# MCU.net
KiCad netlist of a schematic drawn in Altium Designer
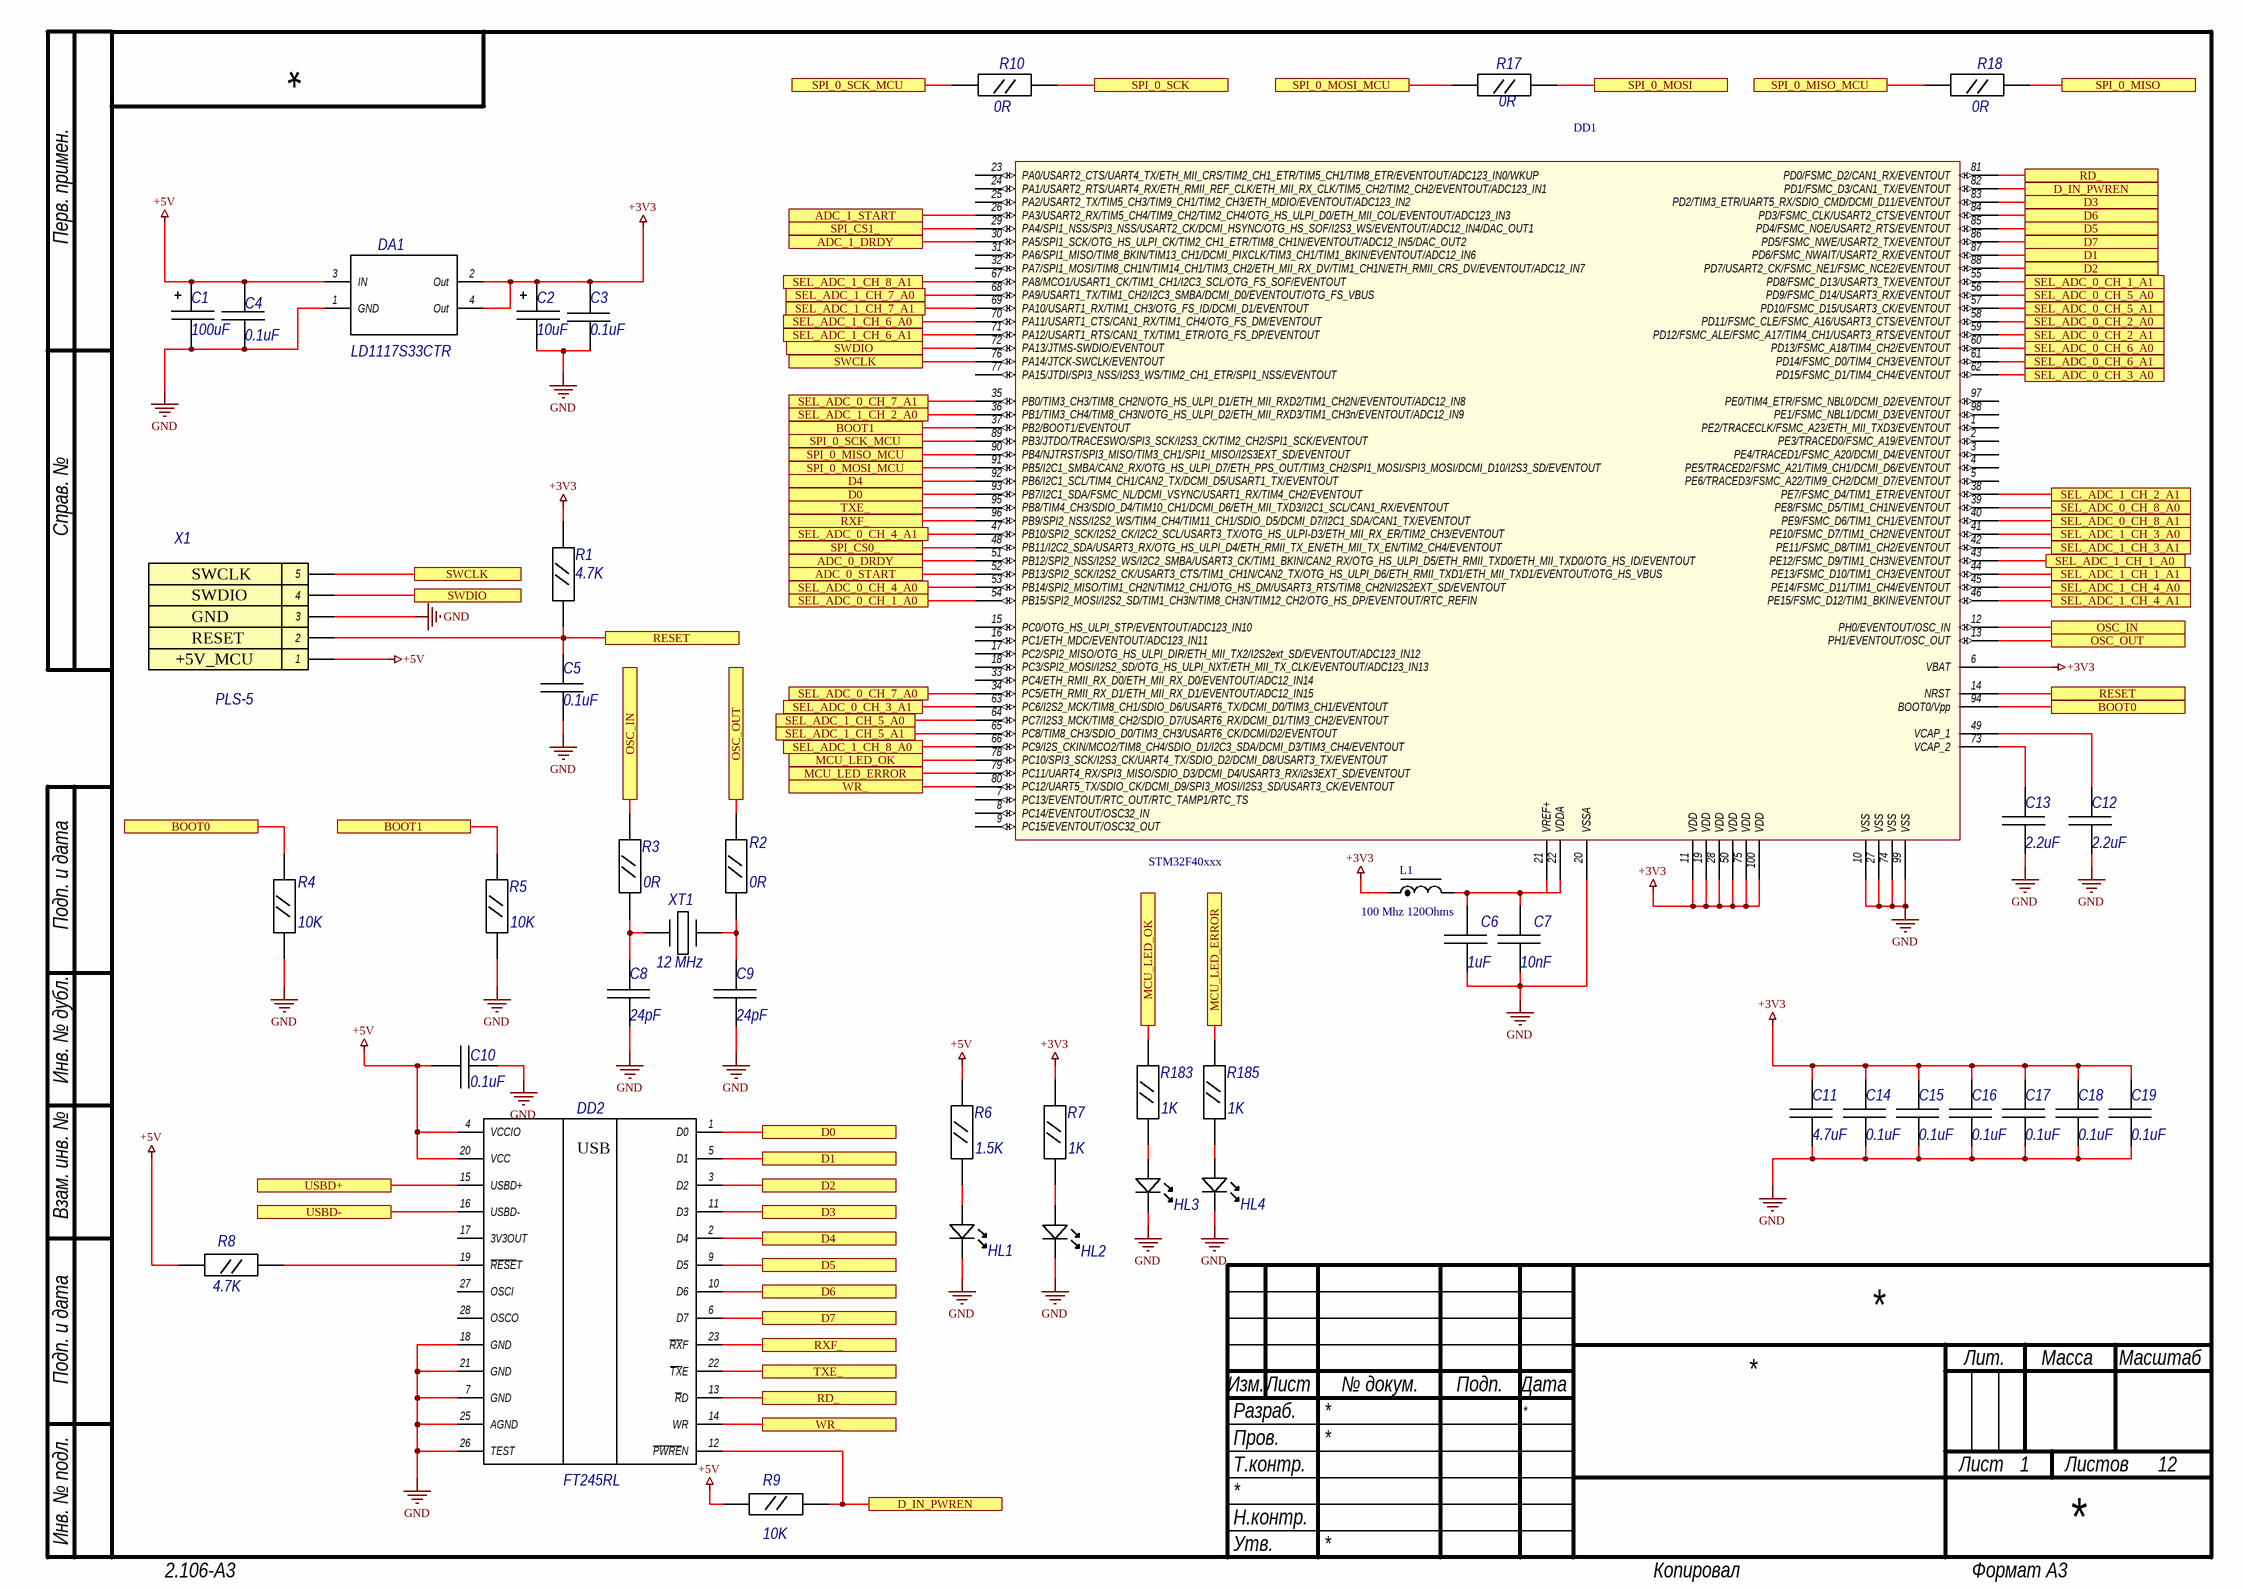
[diagram p0: MCU.SchDoc]

(export (version "E")
  (design (tool "Eeschema 10.0.6"))
  (components
    (comp (ref "C1")
      (value "100uF")
      (footprint "CT_SMD_A")
      (description "Capacitor tantalum")
      (libsource (lib "GOST") (part "CT_SMD_A"))
    )
    (comp (ref "C2")
      (value "10uF")
      (footprint "CT_SMD_A")
      (description "Capacitor tantalum")
      (libsource (lib "GOST") (part "CT_SMD_A"))
    )
    (comp (ref "C3")
      (value "0.1uF")
      (footprint "C0603")
      (description "Ceramic Capacitor SMD")
      (libsource (lib "GOST") (part "CC_SMD_0603"))
    )
    (comp (ref "C4")
      (value "0.1uF")
      (footprint "C0603")
      (description "Ceramic Capacitor SMD")
      (libsource (lib "GOST") (part "CC_SMD_0603"))
    )
    (comp (ref "C5")
      (value "0.1uF")
      (footprint "C0603")
      (description "Ceramic Capacitor SMD")
      (libsource (lib "GOST") (part "CC_SMD_0603"))
    )
    (comp (ref "C6")
      (value "1uF")
      (footprint "C0603")
      (description "Ceramic Capacitor SMD")
      (libsource (lib "GOST") (part "CC_SMD_0603"))
    )
    (comp (ref "C7")
      (value "10nF")
      (footprint "C0603")
      (description "Ceramic Capacitor SMD")
      (libsource (lib "GOST") (part "CC_SMD_0603"))
    )
    (comp (ref "C8")
      (value "24pF")
      (footprint "C0603")
      (description "Ceramic Capacitor SMD")
      (libsource (lib "GOST") (part "CC_SMD_0603"))
    )
    (comp (ref "C9")
      (value "24pF")
      (footprint "C0603")
      (description "Ceramic Capacitor SMD")
      (libsource (lib "GOST") (part "CC_SMD_0603"))
    )
    (comp (ref "C10")
      (value "0.1uF")
      (footprint "C0603")
      (description "Ceramic Capacitor SMD")
      (libsource (lib "GOST") (part "CC_SMD_0603"))
    )
    (comp (ref "C11")
      (value "4.7uF")
      (footprint "C0603")
      (description "Ceramic Capacitor SMD")
      (libsource (lib "GOST") (part "CC_SMD_0603"))
    )
    (comp (ref "C12")
      (value "2.2uF")
      (footprint "C0603")
      (description "Ceramic Capacitor SMD")
      (libsource (lib "GOST") (part "CC_SMD_0603"))
    )
    (comp (ref "C13")
      (value "2.2uF")
      (footprint "C0603")
      (description "Ceramic Capacitor SMD")
      (libsource (lib "GOST") (part "CC_SMD_0603"))
    )
    (comp (ref "C14")
      (value "0.1uF")
      (footprint "C0603")
      (description "Ceramic Capacitor SMD")
      (libsource (lib "GOST") (part "CC_SMD_0603"))
    )
    (comp (ref "C15")
      (value "0.1uF")
      (footprint "C0603")
      (description "Ceramic Capacitor SMD")
      (libsource (lib "GOST") (part "CC_SMD_0603"))
    )
    (comp (ref "C16")
      (value "0.1uF")
      (footprint "C0603")
      (description "Ceramic Capacitor SMD")
      (libsource (lib "GOST") (part "CC_SMD_0603"))
    )
    (comp (ref "C17")
      (value "0.1uF")
      (footprint "C0603")
      (description "Ceramic Capacitor SMD")
      (libsource (lib "GOST") (part "CC_SMD_0603"))
    )
    (comp (ref "C18")
      (value "0.1uF")
      (footprint "C0603")
      (description "Ceramic Capacitor SMD")
      (libsource (lib "GOST") (part "CC_SMD_0603"))
    )
    (comp (ref "C19")
      (value "0.1uF")
      (footprint "C0603")
      (description "Ceramic Capacitor SMD")
      (libsource (lib "GOST") (part "CC_SMD_0603"))
    )
    (comp (ref "DA1")
      (value "LD1117S33CTR")
      (footprint "SOT-223(DCY)")
      (description "LDO")
      (libsource (lib "GOST") (part "LD1117S33CTR"))
    )
    (comp (ref "DD1")
      (value "STM32F40xxx")
      (footprint "QFP50P1600X1600X160-100N")
      (description "ARM CortexM4 32b")
      (libsource (lib "GOST") (part "STM32F40xxx"))
    )
    (comp (ref "DD2")
      (value "FT245RL")
      (footprint "SSOP-28N")
      (description "USB to parallel FIFO interface")
      (fields (field (name "MANUFACTURER") "FTDI"))
      (libsource (lib "GOST") (part "FT245RL"))
    )
    (comp (ref "HL1")
      (value "GREEN")
      (footprint "LED_0603")
      (description "LED GREEN SMD 0603")
      (fields (field (name "PARTNUMBER") "FYLS-0603PGC"))
      (libsource (lib "GOST") (part "LED_G_SMD_0603"))
    )
    (comp (ref "HL2")
      (value "GREEN")
      (footprint "LED_0603")
      (description "LED GREEN SMD 0603")
      (fields (field (name "PARTNUMBER") "FYLS-0603PGC"))
      (libsource (lib "GOST") (part "LED_G_SMD_0603"))
    )
    (comp (ref "HL3")
      (value "GREEN")
      (footprint "LED_0603")
      (description "LED GREEN SMD 0603")
      (fields (field (name "PARTNUMBER") "FYLS-0603PGC"))
      (libsource (lib "GOST") (part "LED_G_SMD_0603"))
    )
    (comp (ref "HL4")
      (value "GREEN")
      (footprint "LED_0603")
      (description "LED GREEN SMD 0603")
      (fields (field (name "PARTNUMBER") "FYLS-0603PGC"))
      (libsource (lib "GOST") (part "LED_G_SMD_0603"))
    )
    (comp (ref "L1")
      (value "100 Mhz 120Ohms")
      (footprint "0805")
      (description "FerriteBead")
      (fields (field (name "PARTNUMBER") "BLM21PG121SN1D"))
      (libsource (lib "GOST") (part "FerriteBead_0805"))
    )
    (comp (ref "R1")
      (value "4.7K")
      (footprint "R0603")
      (description "Resistor SMD")
      (libsource (lib "GOST") (part "R0603"))
    )
    (comp (ref "R2")
      (value "0R")
      (footprint "R0603")
      (description "Resistor SMD")
      (libsource (lib "GOST") (part "R0603"))
    )
    (comp (ref "R3")
      (value "0R")
      (footprint "R0603")
      (description "Resistor SMD")
      (libsource (lib "GOST") (part "R0603"))
    )
    (comp (ref "R4")
      (value "10K")
      (footprint "R0603")
      (description "Resistor SMD")
      (libsource (lib "GOST") (part "R0603"))
    )
    (comp (ref "R5")
      (value "10K")
      (footprint "R0603")
      (description "Resistor SMD")
      (libsource (lib "GOST") (part "R0603"))
    )
    (comp (ref "R6")
      (value "1.5K")
      (footprint "R0603")
      (description "Resistor SMD")
      (libsource (lib "GOST") (part "R0603"))
    )
    (comp (ref "R7")
      (value "1K")
      (footprint "R0603")
      (description "Resistor SMD")
      (libsource (lib "GOST") (part "R0603"))
    )
    (comp (ref "R8")
      (value "4.7K")
      (footprint "R0603")
      (description "Resistor SMD")
      (libsource (lib "GOST") (part "R0603"))
    )
    (comp (ref "R9")
      (value "10K")
      (footprint "R0603")
      (description "Resistor SMD")
      (libsource (lib "GOST") (part "R0603"))
    )
    (comp (ref "R10")
      (value "0R")
      (footprint "R0603")
      (description "Resistor SMD")
      (libsource (lib "") (part "R0603_1"))
    )
    (comp (ref "R17")
      (value "0R")
      (footprint "R0603")
      (description "Resistor SMD")
      (libsource (lib "") (part "R0603_1"))
    )
    (comp (ref "R18")
      (value "0R")
      (footprint "R0603")
      (description "Resistor SMD")
      (libsource (lib "") (part "R0603_1"))
    )
    (comp (ref "R183")
      (value "1K")
      (footprint "R0603")
      (description "Resistor SMD")
      (libsource (lib "GOST") (part "R0603"))
    )
    (comp (ref "R185")
      (value "1K")
      (footprint "R0603")
      (description "Resistor SMD")
      (libsource (lib "GOST") (part "R0603"))
    )
    (comp (ref "X1")
      (value "PLS-5")
      (footprint "PLS-5")
      (description "5 pin connector, 2.54 step")
      (fields (field (name "PARTNUMBER") "825433-5"))
      (libsource (lib "GOST") (part "PLS-5"))
    )
    (comp (ref "XT1")
      (value "12 MHz")
      (footprint "HC49/US")
      (description "Quarz ESR 50 Ohms, Frequency Stability ±30ppm, Load Capacitance 18 pF")
      (fields (field (name "PARTNUMBER") "J49SML-F-G-G-K-12M0"))
      (libsource (lib "GOST") (part "Quarz HC-49/US 12 MHz"))
    )
  )
  (nets
    (net (code "1") (name "+3V3") (class "Default")
      (node (ref "C11") (pin "2") (pinfunction "2_2") (pintype "passive"))
      (node (ref "C14") (pin "2") (pinfunction "2_2") (pintype "passive"))
      (node (ref "C15") (pin "2") (pinfunction "2_2") (pintype "passive"))
      (node (ref "C16") (pin "2") (pinfunction "2_2") (pintype "passive"))
      (node (ref "C17") (pin "2") (pinfunction "2_2") (pintype "passive"))
      (node (ref "C18") (pin "2") (pinfunction "2_2") (pintype "passive"))
      (node (ref "C19") (pin "2") (pinfunction "2_2") (pintype "passive"))
      (node (ref "C2") (pin "1") (pinfunction "1_1") (pintype "passive"))
      (node (ref "C3") (pin "2") (pinfunction "2_2") (pintype "passive"))
      (node (ref "DA1") (pin "2") (pinfunction "Out_2") (pintype "passive"))
      (node (ref "DA1") (pin "4") (pinfunction "Out_4") (pintype "passive"))
      (node (ref "DD1") (pin "100") (pinfunction "VDD_100") (pintype "power_in"))
      (node (ref "DD1") (pin "11") (pinfunction "VDD_11") (pintype "power_in"))
      (node (ref "DD1") (pin "19") (pinfunction "VDD_19") (pintype "power_in"))
      (node (ref "DD1") (pin "28") (pinfunction "VDD_28") (pintype "power_in"))
      (node (ref "DD1") (pin "50") (pinfunction "VDD_50") (pintype "power_in"))
      (node (ref "DD1") (pin "6") (pinfunction "VBAT_6") (pintype "power_in"))
      (node (ref "DD1") (pin "75") (pinfunction "VDD_75") (pintype "power_in"))
      (node (ref "L1") (pin "1") (pinfunction "1_1") (pintype "passive"))
      (node (ref "R1") (pin "2") (pinfunction "2_2") (pintype "passive"))
      (node (ref "R7") (pin "2") (pinfunction "2_2") (pintype "passive"))
    )
    (net (code "2") (name "+5V") (class "Default")
      (node (ref "C1") (pin "1") (pinfunction "1_1") (pintype "passive"))
      (node (ref "C10") (pin "2") (pinfunction "2_2") (pintype "passive"))
      (node (ref "C4") (pin "2") (pinfunction "2_2") (pintype "passive"))
      (node (ref "DA1") (pin "3") (pinfunction "IN_3") (pintype "power_in"))
      (node (ref "DD2") (pin "20") (pinfunction "VCC_20") (pintype "passive"))
      (node (ref "DD2") (pin "4") (pinfunction "VCCIO_4") (pintype "passive"))
      (node (ref "R6") (pin "2") (pinfunction "2_2") (pintype "passive"))
      (node (ref "R8") (pin "2") (pinfunction "2_2") (pintype "passive"))
      (node (ref "R9") (pin "1") (pinfunction "1_1") (pintype "passive"))
      (node (ref "X1") (pin "1") (pinfunction "1_1") (pintype "passive"))
    )
    (net (code "3") (name "/ADC_0_DRDY") (class "Default")
      (node (ref "DD1") (pin "51") (pinfunction "PB12/SPI2_NSS/I2S2_WS/I2C2_SMBA/USART3_CK/TIM1_BKIN/CAN2_RX/OTG_HS_ULPI_D5/ETH_RMII_TXD0/ETH_MII_TXD0/OTG_HS_ID/EVENTOUT_51") (pintype "bidirectional"))
    )
    (net (code "4") (name "/ADC_0_START") (class "Default")
      (node (ref "DD1") (pin "52") (pinfunction "PB13/SPI2_SCK/I2S2_CK/USART3_CTS/TIM1_CH1N/CAN2_TX/OTG_HS_ULPI_D6/ETH_RMII_TXD1/ETH_MII_TXD1/EVENTOUT/OTG_HS_VBUS_52") (pintype "bidirectional"))
    )
    (net (code "5") (name "/ADC_1_DRDY") (class "Default")
      (node (ref "DD1") (pin "30") (pinfunction "PA5/SPI1_SCK/OTG_HS_ULPI_CK/TIM2_CH1_ETR/TIM8_CH1N/EVENTOUT/ADC12_IN5/DAC_OUT2_30") (pintype "bidirectional"))
    )
    (net (code "6") (name "/ADC_1_START") (class "Default")
      (node (ref "DD1") (pin "26") (pinfunction "PA3/USART2_RX/TIM5_CH4/TIM9_CH2/TIM2_CH4/OTG_HS_ULPI_D0/ETH_MII_COL/EVENTOUT/ADC123_IN3_26") (pintype "bidirectional"))
    )
    (net (code "7") (name "/BOOT0") (class "Default")
      (node (ref "DD1") (pin "94") (pinfunction "BOOT0/Vpp_94") (pintype "power_in"))
      (node (ref "R4") (pin "2") (pinfunction "2_2") (pintype "passive"))
    )
    (net (code "8") (name "/BOOT1") (class "Default")
      (node (ref "DD1") (pin "37") (pinfunction "PB2/BOOT1/EVENTOUT_37") (pintype "bidirectional"))
      (node (ref "R5") (pin "2") (pinfunction "2_2") (pintype "passive"))
    )
    (net (code "9") (name "/D0") (class "Default")
      (node (ref "DD1") (pin "93") (pinfunction "PB7/I2C1_SDA/FSMC_NL/DCMI_VSYNC/USART1_RX/TIM4_CH2/EVENTOUT_93") (pintype "bidirectional"))
      (node (ref "DD2") (pin "1") (pinfunction "D0_1") (pintype "passive"))
    )
    (net (code "10") (name "/D1") (class "Default")
      (node (ref "DD1") (pin "87") (pinfunction "PD6/FSMC_NWAIT/USART2_RX/EVENTOUT_87") (pintype "bidirectional"))
      (node (ref "DD2") (pin "5") (pinfunction "D1_5") (pintype "passive"))
    )
    (net (code "11") (name "/D2") (class "Default")
      (node (ref "DD1") (pin "88") (pinfunction "PD7/USART2_CK/FSMC_NE1/FSMC_NCE2/EVENTOUT_88") (pintype "bidirectional"))
      (node (ref "DD2") (pin "3") (pinfunction "D2_3") (pintype "passive"))
    )
    (net (code "12") (name "/D3") (class "Default")
      (node (ref "DD1") (pin "83") (pinfunction "PD2/TIM3_ETR/UART5_RX/SDIO_CMD/DCMI_D11/EVENTOUT_83") (pintype "bidirectional"))
      (node (ref "DD2") (pin "11") (pinfunction "D3_11") (pintype "passive"))
    )
    (net (code "13") (name "/D4") (class "Default")
      (node (ref "DD1") (pin "92") (pinfunction "PB6/I2C1_SCL/TIM4_CH1/CAN2_TX/DCMI_D5/USART1_TX/EVENTOUT_92") (pintype "bidirectional"))
      (node (ref "DD2") (pin "2") (pinfunction "D4_2") (pintype "passive"))
    )
    (net (code "14") (name "/D5") (class "Default")
      (node (ref "DD1") (pin "85") (pinfunction "PD4/FSMC_NOE/USART2_RTS/EVENTOUT_85") (pintype "bidirectional"))
      (node (ref "DD2") (pin "9") (pinfunction "D5_9") (pintype "passive"))
    )
    (net (code "15") (name "/D6") (class "Default")
      (node (ref "DD1") (pin "84") (pinfunction "PD3/FSMC_CLK/USART2_CTS/EVENTOUT_84") (pintype "bidirectional"))
      (node (ref "DD2") (pin "10") (pinfunction "D6_10") (pintype "passive"))
    )
    (net (code "16") (name "/D7") (class "Default")
      (node (ref "DD1") (pin "86") (pinfunction "PD5/FSMC_NWE/USART2_TX/EVENTOUT_86") (pintype "bidirectional"))
      (node (ref "DD2") (pin "6") (pinfunction "D7_6") (pintype "passive"))
    )
    (net (code "17") (name "/D_IN_PWREN") (class "Default")
      (node (ref "DD1") (pin "82") (pinfunction "PD1/FSMC_D3/CAN1_TX/EVENTOUT_82") (pintype "bidirectional"))
      (node (ref "DD2") (pin "12") (pinfunction "~{PWRE}N_12") (pintype "passive"))
      (node (ref "R9") (pin "2") (pinfunction "2_2") (pintype "passive"))
    )
    (net (code "18") (name "/MCU_LED_ERROR") (class "Default")
      (node (ref "DD1") (pin "79") (pinfunction "PC11/UART4_RX/SPI3_MISO/SDIO_D3/DCMI_D4/USART3_RX/i2s3EXT_SD/EVENTOUT_79") (pintype "bidirectional"))
      (node (ref "R185") (pin "2") (pinfunction "2_2") (pintype "passive"))
    )
    (net (code "19") (name "/MCU_LED_OK") (class "Default")
      (node (ref "DD1") (pin "78") (pinfunction "PC10/SPI3_SCK/I2S3_CK/UART4_TX/SDIO_D2/DCMI_D8/USART3_TX/EVENTOUT_78") (pintype "bidirectional"))
      (node (ref "R183") (pin "2") (pinfunction "2_2") (pintype "passive"))
    )
    (net (code "20") (name "/OSC_IN") (class "Default")
      (node (ref "DD1") (pin "12") (pinfunction "PH0/EVENTOUT/OSC_IN_12") (pintype "bidirectional"))
      (node (ref "R3") (pin "2") (pinfunction "2_2") (pintype "passive"))
    )
    (net (code "21") (name "/OSC_OUT") (class "Default")
      (node (ref "DD1") (pin "13") (pinfunction "PH1/EVENTOUT/OSC_OUT_13") (pintype "bidirectional"))
      (node (ref "R2") (pin "2") (pinfunction "2_2") (pintype "passive"))
    )
    (net (code "22") (name "/RD_") (class "Default")
      (node (ref "DD1") (pin "81") (pinfunction "PD0/FSMC_D2/CAN1_RX/EVENTOUT_81") (pintype "bidirectional"))
      (node (ref "DD2") (pin "13") (pinfunction "~{R}D_13") (pintype "passive"))
    )
    (net (code "23") (name "/RESET") (class "Default")
      (node (ref "C5") (pin "2") (pinfunction "2_2") (pintype "passive"))
      (node (ref "DD1") (pin "14") (pinfunction "NRST_14") (pintype "power_in"))
      (node (ref "R1") (pin "1") (pinfunction "1_1") (pintype "passive"))
      (node (ref "X1") (pin "2") (pinfunction "2_2") (pintype "passive"))
    )
    (net (code "24") (name "/RXF_") (class "Default")
      (node (ref "DD1") (pin "96") (pinfunction "PB9/SPI2_NSS/I2S2_WS/TIM4_CH4/TIM11_CH1/SDIO_D5/DCMI_D7/I2C1_SDA/CAN1_TX/EVENTOUT_96") (pintype "bidirectional"))
      (node (ref "DD2") (pin "23") (pinfunction "~{RX}F_23") (pintype "passive"))
    )
    (net (code "25") (name "/SEL_ADC_0_CH_1_A0") (class "Default")
      (node (ref "DD1") (pin "54") (pinfunction "PB15/SPI2_MOSI/I2S2_SD/TIM1_CH3N/TIM8_CH3N/TIM12_CH2/OTG_HS_DP/EVENTOUT/RTC_REFIN_54") (pintype "bidirectional"))
    )
    (net (code "26") (name "/SEL_ADC_0_CH_1_A1") (class "Default")
      (node (ref "DD1") (pin "55") (pinfunction "PD8/FSMC_D13/USART3_TX/EVENTOUT_55") (pintype "bidirectional"))
    )
    (net (code "27") (name "/SEL_ADC_0_CH_2_A0") (class "Default")
      (node (ref "DD1") (pin "58") (pinfunction "PD11/FSMC_CLE/FSMC_A16/USART3_CTS/EVENTOUT_58") (pintype "bidirectional"))
    )
    (net (code "28") (name "/SEL_ADC_0_CH_2_A1") (class "Default")
      (node (ref "DD1") (pin "59") (pinfunction "PD12/FSMC_ALE/FSMC_A17/TIM4_CH1/USART3_RTS/EVENTOUT_59") (pintype "bidirectional"))
    )
    (net (code "29") (name "/SEL_ADC_0_CH_3_A0") (class "Default")
      (node (ref "DD1") (pin "62") (pinfunction "PD15/FSMC_D1/TIM4_CH4/EVENTOUT_62") (pintype "bidirectional"))
    )
    (net (code "30") (name "/SEL_ADC_0_CH_3_A1") (class "Default")
      (node (ref "DD1") (pin "63") (pinfunction "PC6/I2S2_MCK/TIM8_CH1/SDIO_D6/USART6_TX/DCMI_D0/TIM3_CH1/EVENTOUT_63") (pintype "bidirectional"))
    )
    (net (code "31") (name "/SEL_ADC_0_CH_4_A0") (class "Default")
      (node (ref "DD1") (pin "53") (pinfunction "PB14/SPI2_MISO/TIM1_CH2N/TIM12_CH1/OTG_HS_DM/USART3_RTS/TIM8_CH2N/I2S2EXT_SD/EVENTOUT_53") (pintype "bidirectional"))
    )
    (net (code "32") (name "/SEL_ADC_0_CH_4_A1") (class "Default")
      (node (ref "DD1") (pin "47") (pinfunction "PB10/SPI2_SCK/I2S2_CK/I2C2_SCL/USART3_TX/OTG_HS_ULPI-D3/ETH_MII_RX_ER/TIM2_CH3/EVENTOUT_47") (pintype "bidirectional"))
    )
    (net (code "33") (name "/SEL_ADC_0_CH_5_A0") (class "Default")
      (node (ref "DD1") (pin "56") (pinfunction "PD9/FSMC_D14/USART3_RX/EVENTOUT_56") (pintype "bidirectional"))
    )
    (net (code "34") (name "/SEL_ADC_0_CH_5_A1") (class "Default")
      (node (ref "DD1") (pin "57") (pinfunction "PD10/FSMC_D15/USART3_CK/EVENTOUT_57") (pintype "bidirectional"))
    )
    (net (code "35") (name "/SEL_ADC_0_CH_6_A0") (class "Default")
      (node (ref "DD1") (pin "60") (pinfunction "PD13/FSMC_A18/TIM4_CH2/EVENTOUT_60") (pintype "bidirectional"))
    )
    (net (code "36") (name "/SEL_ADC_0_CH_6_A1") (class "Default")
      (node (ref "DD1") (pin "61") (pinfunction "PD14/FSMC_D0/TIM4_CH3/EVENTOUT_61") (pintype "bidirectional"))
    )
    (net (code "37") (name "/SEL_ADC_0_CH_7_A0") (class "Default")
      (node (ref "DD1") (pin "34") (pinfunction "PC5/ETH_RMII_RX_D1/ETH_MII_RX_D1/EVENTOUT/ADC12_IN15_34") (pintype "bidirectional"))
    )
    (net (code "38") (name "/SEL_ADC_0_CH_7_A1") (class "Default")
      (node (ref "DD1") (pin "35") (pinfunction "PB0/TIM3_CH3/TIM8_CH2N/OTG_HS_ULPI_D1/ETH_MII_RXD2/TIM1_CH2N/EVENTOUT/ADC12_IN8_35") (pintype "bidirectional"))
    )
    (net (code "39") (name "/SEL_ADC_0_CH_8_A0") (class "Default")
      (node (ref "DD1") (pin "39") (pinfunction "PE8/FSMC_D5/TIM1_CH1N/EVENTOUT_39") (pintype "bidirectional"))
    )
    (net (code "40") (name "/SEL_ADC_0_CH_8_A1") (class "Default")
      (node (ref "DD1") (pin "40") (pinfunction "PE9/FSMC_D6/TIM1_CH1/EVENTOUT_40") (pintype "bidirectional"))
    )
    (net (code "41") (name "/SEL_ADC_1_CH_1_A0") (class "Default")
      (node (ref "DD1") (pin "43") (pinfunction "PE12/FSMC_D9/TIM1_CH3N/EVENTOUT_43") (pintype "bidirectional"))
    )
    (net (code "42") (name "/SEL_ADC_1_CH_1_A1") (class "Default")
      (node (ref "DD1") (pin "44") (pinfunction "PE13/FSMC_D10/TIM1_CH3/EVENTOUT_44") (pintype "bidirectional"))
    )
    (net (code "43") (name "/SEL_ADC_1_CH_2_A0") (class "Default")
      (node (ref "DD1") (pin "36") (pinfunction "PB1/TIM3_CH4/TIM8_CH3N/OTG_HS_ULPI_D2/ETH_MII_RXD3/TIM1_CH3n/EVENTOUT/ADC12_IN9_36") (pintype "bidirectional"))
    )
    (net (code "44") (name "/SEL_ADC_1_CH_2_A1") (class "Default")
      (node (ref "DD1") (pin "38") (pinfunction "PE7/FSMC_D4/TIM1_ETR/EVENTOUT_38") (pintype "bidirectional"))
    )
    (net (code "45") (name "/SEL_ADC_1_CH_3_A0") (class "Default")
      (node (ref "DD1") (pin "41") (pinfunction "PE10/FSMC_D7/TIM1_CH2N/EVENTOUT_41") (pintype "bidirectional"))
    )
    (net (code "46") (name "/SEL_ADC_1_CH_3_A1") (class "Default")
      (node (ref "DD1") (pin "42") (pinfunction "PE11/FSMC_D8/TIM1_CH2/EVENTOUT_42") (pintype "bidirectional"))
    )
    (net (code "47") (name "/SEL_ADC_1_CH_4_A0") (class "Default")
      (node (ref "DD1") (pin "45") (pinfunction "PE14/FSMC_D11/TIM1_CH4/EVENTOUT_45") (pintype "bidirectional"))
    )
    (net (code "48") (name "/SEL_ADC_1_CH_4_A1") (class "Default")
      (node (ref "DD1") (pin "46") (pinfunction "PE15/FSMC_D12/TIM1_BKIN/EVENTOUT_46") (pintype "bidirectional"))
    )
    (net (code "49") (name "/SEL_ADC_1_CH_5_A0") (class "Default")
      (node (ref "DD1") (pin "64") (pinfunction "PC7/I2S3_MCK/TIM8_CH2/SDIO_D7/USART6_RX/DCMI_D1/TIM3_CH2/EVENTOUT_64") (pintype "bidirectional"))
    )
    (net (code "50") (name "/SEL_ADC_1_CH_5_A1") (class "Default")
      (node (ref "DD1") (pin "65") (pinfunction "PC8/TIM8_CH3/SDIO_D0/TIM3_CH3/USART6_CK/DCMI/D2/EVENTOUT_65") (pintype "bidirectional"))
    )
    (net (code "51") (name "/SEL_ADC_1_CH_6_A0") (class "Default")
      (node (ref "DD1") (pin "70") (pinfunction "PA11/USART1_CTS/CAN1_RX/TIM1_CH4/OTG_FS_DM/EVENTOUT_70") (pintype "bidirectional"))
    )
    (net (code "52") (name "/SEL_ADC_1_CH_6_A1") (class "Default")
      (node (ref "DD1") (pin "71") (pinfunction "PA12/USART1_RTS/CAN1_TX/TIM1_ETR/OTG_FS_DP/EVENTOUT_71") (pintype "bidirectional"))
    )
    (net (code "53") (name "/SEL_ADC_1_CH_7_A0") (class "Default")
      (node (ref "DD1") (pin "68") (pinfunction "PA9/USART1_TX/TIM1_CH2/I2C3_SMBA/DCMI_D0/EVENTOUT/OTG_FS_VBUS_68") (pintype "bidirectional"))
    )
    (net (code "54") (name "/SEL_ADC_1_CH_7_A1") (class "Default")
      (node (ref "DD1") (pin "69") (pinfunction "PA10/USART1_RX/TIM1_CH3/OTG_FS_ID/DCMI_D1/EVENTOUT_69") (pintype "bidirectional"))
    )
    (net (code "55") (name "/SEL_ADC_1_CH_8_A0") (class "Default")
      (node (ref "DD1") (pin "66") (pinfunction "PC9/I2S_CKIN/MCO2/TIM8_CH4/SDIO_D1/I2C3_SDA/DCMI_D3/TIM3_CH4/EVENTOUT_66") (pintype "bidirectional"))
    )
    (net (code "56") (name "/SEL_ADC_1_CH_8_A1") (class "Default")
      (node (ref "DD1") (pin "67") (pinfunction "PA8/MCO1/USART1_CK/TIM1_CH1/I2C3_SCL/OTG_FS_SOF/EVENTOUT_67") (pintype "bidirectional"))
    )
    (net (code "57") (name "/SPI_0_MISO") (class "Default")
      (node (ref "R18") (pin "1") (pinfunction "1_1") (pintype "passive"))
    )
    (net (code "58") (name "/SPI_0_MISO_MCU") (class "Default")
      (node (ref "DD1") (pin "90") (pinfunction "PB4/NJTRST/SPI3_MISO/TIM3_CH1/SPI1_MISO/I2S3EXT_SD/EVENTOUT_90") (pintype "bidirectional"))
      (node (ref "R18") (pin "2") (pinfunction "2_2") (pintype "passive"))
    )
    (net (code "59") (name "/SPI_0_MOSI") (class "Default")
      (node (ref "R17") (pin "1") (pinfunction "1_1") (pintype "passive"))
    )
    (net (code "60") (name "/SPI_0_MOSI_MCU") (class "Default")
      (node (ref "DD1") (pin "91") (pinfunction "PB5/I2C1_SMBA/CAN2_RX/OTG_HS_ULPI_D7/ETH_PPS_OUT/TIM3_CH2/SPI1_MOSI/SPI3_MOSI/DCMI_D10/I2S3_SD/EVENTOUT_91") (pintype "bidirectional"))
      (node (ref "R17") (pin "2") (pinfunction "2_2") (pintype "passive"))
    )
    (net (code "61") (name "/SPI_0_SCK") (class "Default")
      (node (ref "R10") (pin "1") (pinfunction "1_1") (pintype "passive"))
    )
    (net (code "62") (name "/SPI_0_SCK_MCU") (class "Default")
      (node (ref "DD1") (pin "89") (pinfunction "PB3/JTDO/TRACESWO/SPI3_SCK/I2S3_CK/TIM2_CH2/SPI1_SCK/EVENTOUT_89") (pintype "bidirectional"))
      (node (ref "R10") (pin "2") (pinfunction "2_2") (pintype "passive"))
    )
    (net (code "63") (name "/SPI_CS0_") (class "Default")
      (node (ref "DD1") (pin "48") (pinfunction "PB11/I2C2_SDA/USART3_RX/OTG_HS_ULPI_D4/ETH_RMII_TX_EN/ETH_MII_TX_EN/TIM2_CH4/EVENTOUT_48") (pintype "bidirectional"))
    )
    (net (code "64") (name "/SPI_CS1_") (class "Default")
      (node (ref "DD1") (pin "29") (pinfunction "PA4/SPI1_NSS/SPI3_NSS/USART2_CK/DCMI_HSYNC/OTG_HS_SOF/I2S3_WS/EVENTOUT/ADC12_IN4/DAC_OUT1_29") (pintype "bidirectional"))
    )
    (net (code "65") (name "/SWCLK") (class "Default")
      (node (ref "DD1") (pin "76") (pinfunction "PA14/JTCK-SWCLK/EVENTOUT_76") (pintype "bidirectional"))
      (node (ref "X1") (pin "5") (pinfunction "5_5") (pintype "passive"))
    )
    (net (code "66") (name "/SWDIO") (class "Default")
      (node (ref "DD1") (pin "72") (pinfunction "PA13/JTMS-SWDIO/EVENTOUT_72") (pintype "bidirectional"))
      (node (ref "X1") (pin "4") (pinfunction "4_4") (pintype "passive"))
    )
    (net (code "67") (name "/TXE_") (class "Default")
      (node (ref "DD1") (pin "95") (pinfunction "PB8/TIM4_CH3/SDIO_D4/TIM10_CH1/DCMI_D6/ETH_MII_TXD3/I2C1_SCL/CAN1_RX/EVENTOUT_95") (pintype "bidirectional"))
      (node (ref "DD2") (pin "22") (pinfunction "~{TX}E_22") (pintype "passive"))
    )
    (net (code "68") (name "/USBD+") (class "Default")
      (node (ref "DD2") (pin "15") (pinfunction "USBD+_15") (pintype "passive"))
    )
    (net (code "69") (name "/USBD-") (class "Default")
      (node (ref "DD2") (pin "16") (pinfunction "USBD-_16") (pintype "passive"))
    )
    (net (code "70") (name "/WR_") (class "Default")
      (node (ref "DD1") (pin "80") (pinfunction "PC12/UART5_TX/SDIO_CK/DCMI_D9/SPI3_MOSI/I2S3_SD/USART3_CK/EVENTOUT_80") (pintype "bidirectional"))
      (node (ref "DD2") (pin "14") (pinfunction "WR_14") (pintype "passive"))
    )
    (net (code "71") (name "GND") (class "Default")
      (node (ref "C1") (pin "2") (pinfunction "2_2") (pintype "passive"))
      (node (ref "C10") (pin "1") (pinfunction "1_1") (pintype "passive"))
      (node (ref "C11") (pin "1") (pinfunction "1_1") (pintype "passive"))
      (node (ref "C12") (pin "1") (pinfunction "1_1") (pintype "passive"))
      (node (ref "C13") (pin "1") (pinfunction "1_1") (pintype "passive"))
      (node (ref "C14") (pin "1") (pinfunction "1_1") (pintype "passive"))
      (node (ref "C15") (pin "1") (pinfunction "1_1") (pintype "passive"))
      (node (ref "C16") (pin "1") (pinfunction "1_1") (pintype "passive"))
      (node (ref "C17") (pin "1") (pinfunction "1_1") (pintype "passive"))
      (node (ref "C18") (pin "1") (pinfunction "1_1") (pintype "passive"))
      (node (ref "C19") (pin "1") (pinfunction "1_1") (pintype "passive"))
      (node (ref "C2") (pin "2") (pinfunction "2_2") (pintype "passive"))
      (node (ref "C3") (pin "1") (pinfunction "1_1") (pintype "passive"))
      (node (ref "C4") (pin "1") (pinfunction "1_1") (pintype "passive"))
      (node (ref "C5") (pin "1") (pinfunction "1_1") (pintype "passive"))
      (node (ref "C6") (pin "1") (pinfunction "1_1") (pintype "passive"))
      (node (ref "C7") (pin "1") (pinfunction "1_1") (pintype "passive"))
      (node (ref "C8") (pin "1") (pinfunction "1_1") (pintype "passive"))
      (node (ref "C9") (pin "1") (pinfunction "1_1") (pintype "passive"))
      (node (ref "DA1") (pin "1") (pinfunction "GND_1") (pintype "passive"))
      (node (ref "DD1") (pin "10") (pinfunction "VSS_10") (pintype "power_in"))
      (node (ref "DD1") (pin "20") (pinfunction "VSSA_20") (pintype "power_in"))
      (node (ref "DD1") (pin "27") (pinfunction "VSS_27") (pintype "power_in"))
      (node (ref "DD1") (pin "74") (pinfunction "VSS_74") (pintype "power_in"))
      (node (ref "DD1") (pin "99") (pinfunction "VSS_99") (pintype "power_in"))
      (node (ref "DD2") (pin "18") (pinfunction "GND_18") (pintype "passive"))
      (node (ref "DD2") (pin "21") (pinfunction "GND_21") (pintype "passive"))
      (node (ref "DD2") (pin "25") (pinfunction "AGND_25") (pintype "passive"))
      (node (ref "DD2") (pin "26") (pinfunction "TEST_26") (pintype "passive"))
      (node (ref "DD2") (pin "7") (pinfunction "GND_7") (pintype "passive"))
      (node (ref "HL1") (pin "K") (pinfunction "K_K") (pintype "passive"))
      (node (ref "HL2") (pin "K") (pinfunction "K_K") (pintype "passive"))
      (node (ref "HL3") (pin "K") (pinfunction "K_K") (pintype "passive"))
      (node (ref "HL4") (pin "K") (pinfunction "K_K") (pintype "passive"))
      (node (ref "R4") (pin "1") (pinfunction "1_1") (pintype "passive"))
      (node (ref "R5") (pin "1") (pinfunction "1_1") (pintype "passive"))
      (node (ref "X1") (pin "3") (pinfunction "3_3") (pintype "passive"))
    )
    (net (code "72") (name "Net-(DD1-VCAP_1)") (class "Default")
      (node (ref "C12") (pin "2") (pinfunction "2_2") (pintype "passive"))
      (node (ref "DD1") (pin "49") (pinfunction "VCAP_1_49") (pintype "power_in"))
    )
    (net (code "73") (name "Net-(DD1-VCAP_2)") (class "Default")
      (node (ref "C13") (pin "2") (pinfunction "2_2") (pintype "passive"))
      (node (ref "DD1") (pin "73") (pinfunction "VCAP_2_73") (pintype "power_in"))
    )
    (net (code "74") (name "Net-(DD1-VDDA)") (class "Default")
      (node (ref "C6") (pin "2") (pinfunction "2_2") (pintype "passive"))
      (node (ref "C7") (pin "2") (pinfunction "2_2") (pintype "passive"))
      (node (ref "DD1") (pin "21") (pinfunction "VREF+_21") (pintype "power_in"))
      (node (ref "DD1") (pin "22") (pinfunction "VDDA_22") (pintype "power_in"))
      (node (ref "L1") (pin "2") (pinfunction "2_2") (pintype "passive"))
    )
    (net (code "75") (name "Net-(DD2-~{RESE}T)") (class "Default")
      (node (ref "DD2") (pin "19") (pinfunction "~{RESE}T_19") (pintype "passive"))
      (node (ref "R8") (pin "1") (pinfunction "1_1") (pintype "passive"))
    )
    (net (code "76") (name "Net-(HL1-PadA)") (class "Default")
      (node (ref "HL1") (pin "A") (pinfunction "A_A") (pintype "passive"))
      (node (ref "R6") (pin "1") (pinfunction "1_1") (pintype "passive"))
    )
    (net (code "77") (name "Net-(HL2-PadA)") (class "Default")
      (node (ref "HL2") (pin "A") (pinfunction "A_A") (pintype "passive"))
      (node (ref "R7") (pin "1") (pinfunction "1_1") (pintype "passive"))
    )
    (net (code "78") (name "Net-(HL3-PadA)") (class "Default")
      (node (ref "HL3") (pin "A") (pinfunction "A_A") (pintype "passive"))
      (node (ref "R183") (pin "1") (pinfunction "1_1") (pintype "passive"))
    )
    (net (code "79") (name "Net-(HL4-PadA)") (class "Default")
      (node (ref "HL4") (pin "A") (pinfunction "A_A") (pintype "passive"))
      (node (ref "R185") (pin "1") (pinfunction "1_1") (pintype "passive"))
    )
    (net (code "80") (name "Net-(XT1-IN)") (class "Default")
      (node (ref "C9") (pin "2") (pinfunction "2_2") (pintype "passive"))
      (node (ref "R2") (pin "1") (pinfunction "1_1") (pintype "passive"))
      (node (ref "XT1") (pin "1") (pinfunction "IN_1") (pintype "passive"))
    )
    (net (code "81") (name "Net-(XT1-OUT)") (class "Default")
      (node (ref "C8") (pin "2") (pinfunction "2_2") (pintype "passive"))
      (node (ref "R3") (pin "1") (pinfunction "1_1") (pintype "passive"))
      (node (ref "XT1") (pin "2") (pinfunction "OUT_2") (pintype "passive"))
    )
    (net (code "82") (name "unconnected-(DD1-PA0{slash}USART2_CTS{slash}UART4_TX{slash}ETH_MII_CRS{slash}TIM2_CH1_ETR{slash}TIM5_CH1{slash}TIM8_ETR{slash}EVENTOUT{slash}ADC123_IN0{slash}WKUP-Pad23)") (class "Default")
      (node (ref "DD1") (pin "23") (pinfunction "PA0/USART2_CTS/UART4_TX/ETH_MII_CRS/TIM2_CH1_ETR/TIM5_CH1/TIM8_ETR/EVENTOUT/ADC123_IN0/WKUP_23") (pintype "bidirectional"))
    )
    (net (code "83") (name "unconnected-(DD1-PA1{slash}USART2_RTS{slash}UART4_RX{slash}ETH_RMII_REF_CLK{slash}ETH_MII_RX_CLK{slash}TIM5_CH2{slash}TIM2_CH2{slash}EVENTOUT{slash}ADC123_IN1-Pad24)") (class "Default")
      (node (ref "DD1") (pin "24") (pinfunction "PA1/USART2_RTS/UART4_RX/ETH_RMII_REF_CLK/ETH_MII_RX_CLK/TIM5_CH2/TIM2_CH2/EVENTOUT/ADC123_IN1_24") (pintype "bidirectional"))
    )
    (net (code "84") (name "unconnected-(DD1-PA2{slash}USART2_TX{slash}TIM5_CH3{slash}TIM9_CH1{slash}TIM2_CH3{slash}ETH_MDIO{slash}EVENTOUT{slash}ADC123_IN2-Pad25)") (class "Default")
      (node (ref "DD1") (pin "25") (pinfunction "PA2/USART2_TX/TIM5_CH3/TIM9_CH1/TIM2_CH3/ETH_MDIO/EVENTOUT/ADC123_IN2_25") (pintype "bidirectional"))
    )
    (net (code "85") (name "unconnected-(DD1-PA6{slash}SPI1_MISO{slash}TIM8_BKIN{slash}TIM13_CH1{slash}DCMI_PIXCLK{slash}TIM3_CH1{slash}TIM1_BKIN{slash}EVENTOUT{slash}ADC12_IN6-Pad31)") (class "Default")
      (node (ref "DD1") (pin "31") (pinfunction "PA6/SPI1_MISO/TIM8_BKIN/TIM13_CH1/DCMI_PIXCLK/TIM3_CH1/TIM1_BKIN/EVENTOUT/ADC12_IN6_31") (pintype "bidirectional"))
    )
    (net (code "86") (name "unconnected-(DD1-PA7{slash}SPI1_MOSI{slash}TIM8_CH1N{slash}TIM14_CH1{slash}TIM3_CH2{slash}ETH_MII_RX_DV{slash}TIM1_CH1N{slash}ETH_RMII_CRS_DV{slash}EVENTOUT{slash}ADC12_IN7-Pad32)") (class "Default")
      (node (ref "DD1") (pin "32") (pinfunction "PA7/SPI1_MOSI/TIM8_CH1N/TIM14_CH1/TIM3_CH2/ETH_MII_RX_DV/TIM1_CH1N/ETH_RMII_CRS_DV/EVENTOUT/ADC12_IN7_32") (pintype "bidirectional"))
    )
    (net (code "87") (name "unconnected-(DD1-PA15{slash}JTDI{slash}SPI3_NSS{slash}I2S3_WS{slash}TIM2_CH1_ETR{slash}SPI1_NSS{slash}EVENTOUT-Pad77)") (class "Default")
      (node (ref "DD1") (pin "77") (pinfunction "PA15/JTDI/SPI3_NSS/I2S3_WS/TIM2_CH1_ETR/SPI1_NSS/EVENTOUT_77") (pintype "bidirectional"))
    )
    (net (code "88") (name "unconnected-(DD1-PC0{slash}OTG_HS_ULPI_STP{slash}EVENTOUT{slash}ADC123_IN10-Pad15)") (class "Default")
      (node (ref "DD1") (pin "15") (pinfunction "PC0/OTG_HS_ULPI_STP/EVENTOUT/ADC123_IN10_15") (pintype "bidirectional"))
    )
    (net (code "89") (name "unconnected-(DD1-PC1{slash}ETH_MDC{slash}EVENTOUT{slash}ADC123_IN11-Pad16)") (class "Default")
      (node (ref "DD1") (pin "16") (pinfunction "PC1/ETH_MDC/EVENTOUT/ADC123_IN11_16") (pintype "bidirectional"))
    )
    (net (code "90") (name "unconnected-(DD1-PC2{slash}SPI2_MISO{slash}OTG_HS_ULPI_DIR{slash}ETH_MII_TX2{slash}I2S2ext_SD{slash}EVENTOUT{slash}ADC123_IN12-Pad17)") (class "Default")
      (node (ref "DD1") (pin "17") (pinfunction "PC2/SPI2_MISO/OTG_HS_ULPI_DIR/ETH_MII_TX2/I2S2ext_SD/EVENTOUT/ADC123_IN12_17") (pintype "bidirectional"))
    )
    (net (code "91") (name "unconnected-(DD1-PC3{slash}SPI2_MOSI{slash}I2S2_SD{slash}OTG_HS_ULPI_NXT{slash}ETH_MII_TX_CLK{slash}EVENTOUT{slash}ADC123_IN13-Pad18)") (class "Default")
      (node (ref "DD1") (pin "18") (pinfunction "PC3/SPI2_MOSI/I2S2_SD/OTG_HS_ULPI_NXT/ETH_MII_TX_CLK/EVENTOUT/ADC123_IN13_18") (pintype "bidirectional"))
    )
    (net (code "92") (name "unconnected-(DD1-PC4{slash}ETH_RMII_RX_D0{slash}ETH_MII_RX_D0{slash}EVENTOUT{slash}ADC12_IN14-Pad33)") (class "Default")
      (node (ref "DD1") (pin "33") (pinfunction "PC4/ETH_RMII_RX_D0/ETH_MII_RX_D0/EVENTOUT/ADC12_IN14_33") (pintype "bidirectional"))
    )
    (net (code "93") (name "unconnected-(DD1-PC13{slash}EVENTOUT{slash}RTC_OUT{slash}RTC_TAMP1{slash}RTC_TS-Pad7)") (class "Default")
      (node (ref "DD1") (pin "7") (pinfunction "PC13/EVENTOUT/RTC_OUT/RTC_TAMP1/RTC_TS_7") (pintype "bidirectional"))
    )
    (net (code "94") (name "unconnected-(DD1-PC14{slash}EVENTOUT{slash}OSC32_IN-Pad8)") (class "Default")
      (node (ref "DD1") (pin "8") (pinfunction "PC14/EVENTOUT/OSC32_IN_8") (pintype "bidirectional"))
    )
    (net (code "95") (name "unconnected-(DD1-PC15{slash}EVENTOUT{slash}OSC32_OUT-Pad9)") (class "Default")
      (node (ref "DD1") (pin "9") (pinfunction "PC15/EVENTOUT/OSC32_OUT_9") (pintype "bidirectional"))
    )
    (net (code "96") (name "unconnected-(DD1-PE0{slash}TIM4_ETR{slash}FSMC_NBL0{slash}DCMI_D2{slash}EVENTOUT-Pad97)") (class "Default")
      (node (ref "DD1") (pin "97") (pinfunction "PE0/TIM4_ETR/FSMC_NBL0/DCMI_D2/EVENTOUT_97") (pintype "bidirectional"))
    )
    (net (code "97") (name "unconnected-(DD1-PE1{slash}FSMC_NBL1{slash}DCMI_D3{slash}EVENTOUT-Pad98)") (class "Default")
      (node (ref "DD1") (pin "98") (pinfunction "PE1/FSMC_NBL1/DCMI_D3/EVENTOUT_98") (pintype "bidirectional"))
    )
    (net (code "98") (name "unconnected-(DD1-PE2{slash}TRACECLK{slash}FSMC_A23{slash}ETH_MII_TXD3{slash}EVENTOUT-Pad1)") (class "Default")
      (node (ref "DD1") (pin "1") (pinfunction "PE2/TRACECLK/FSMC_A23/ETH_MII_TXD3/EVENTOUT_1") (pintype "bidirectional"))
    )
    (net (code "99") (name "unconnected-(DD1-PE3{slash}TRACED0{slash}FSMC_A19{slash}EVENTOUT-Pad2)") (class "Default")
      (node (ref "DD1") (pin "2") (pinfunction "PE3/TRACED0/FSMC_A19/EVENTOUT_2") (pintype "bidirectional"))
    )
    (net (code "100") (name "unconnected-(DD1-PE4{slash}TRACED1{slash}FSMC_A20{slash}DCMI_D4{slash}EVENTOUT-Pad3)") (class "Default")
      (node (ref "DD1") (pin "3") (pinfunction "PE4/TRACED1/FSMC_A20/DCMI_D4/EVENTOUT_3") (pintype "bidirectional"))
    )
    (net (code "101") (name "unconnected-(DD1-PE5{slash}TRACED2{slash}FSMC_A21{slash}TIM9_CH1{slash}DCMI_D6{slash}EVENTOUT-Pad4)") (class "Default")
      (node (ref "DD1") (pin "4") (pinfunction "PE5/TRACED2/FSMC_A21/TIM9_CH1/DCMI_D6/EVENTOUT_4") (pintype "bidirectional"))
    )
    (net (code "102") (name "unconnected-(DD1-PE6{slash}TRACED3{slash}FSMC_A22{slash}TIM9_CH2{slash}DCMI_D7{slash}EVENTOUT-Pad5)") (class "Default")
      (node (ref "DD1") (pin "5") (pinfunction "PE6/TRACED3/FSMC_A22/TIM9_CH2/DCMI_D7/EVENTOUT_5") (pintype "bidirectional"))
    )
    (net (code "103") (name "unconnected-(DD2-3V3OUT-Pad17)") (class "Default")
      (node (ref "DD2") (pin "17") (pinfunction "3V3OUT_17") (pintype "passive"))
    )
    (net (code "104") (name "unconnected-(DD2-OSCI-Pad27)") (class "Default")
      (node (ref "DD2") (pin "27") (pinfunction "OSCI_27") (pintype "passive"))
    )
    (net (code "105") (name "unconnected-(DD2-OSCO-Pad28)") (class "Default")
      (node (ref "DD2") (pin "28") (pinfunction "OSCO_28") (pintype "passive"))
    )
  )
)
